# ATSAMD21_breakout_test.net
KiCad netlist of a schematic drawn in EAGLE
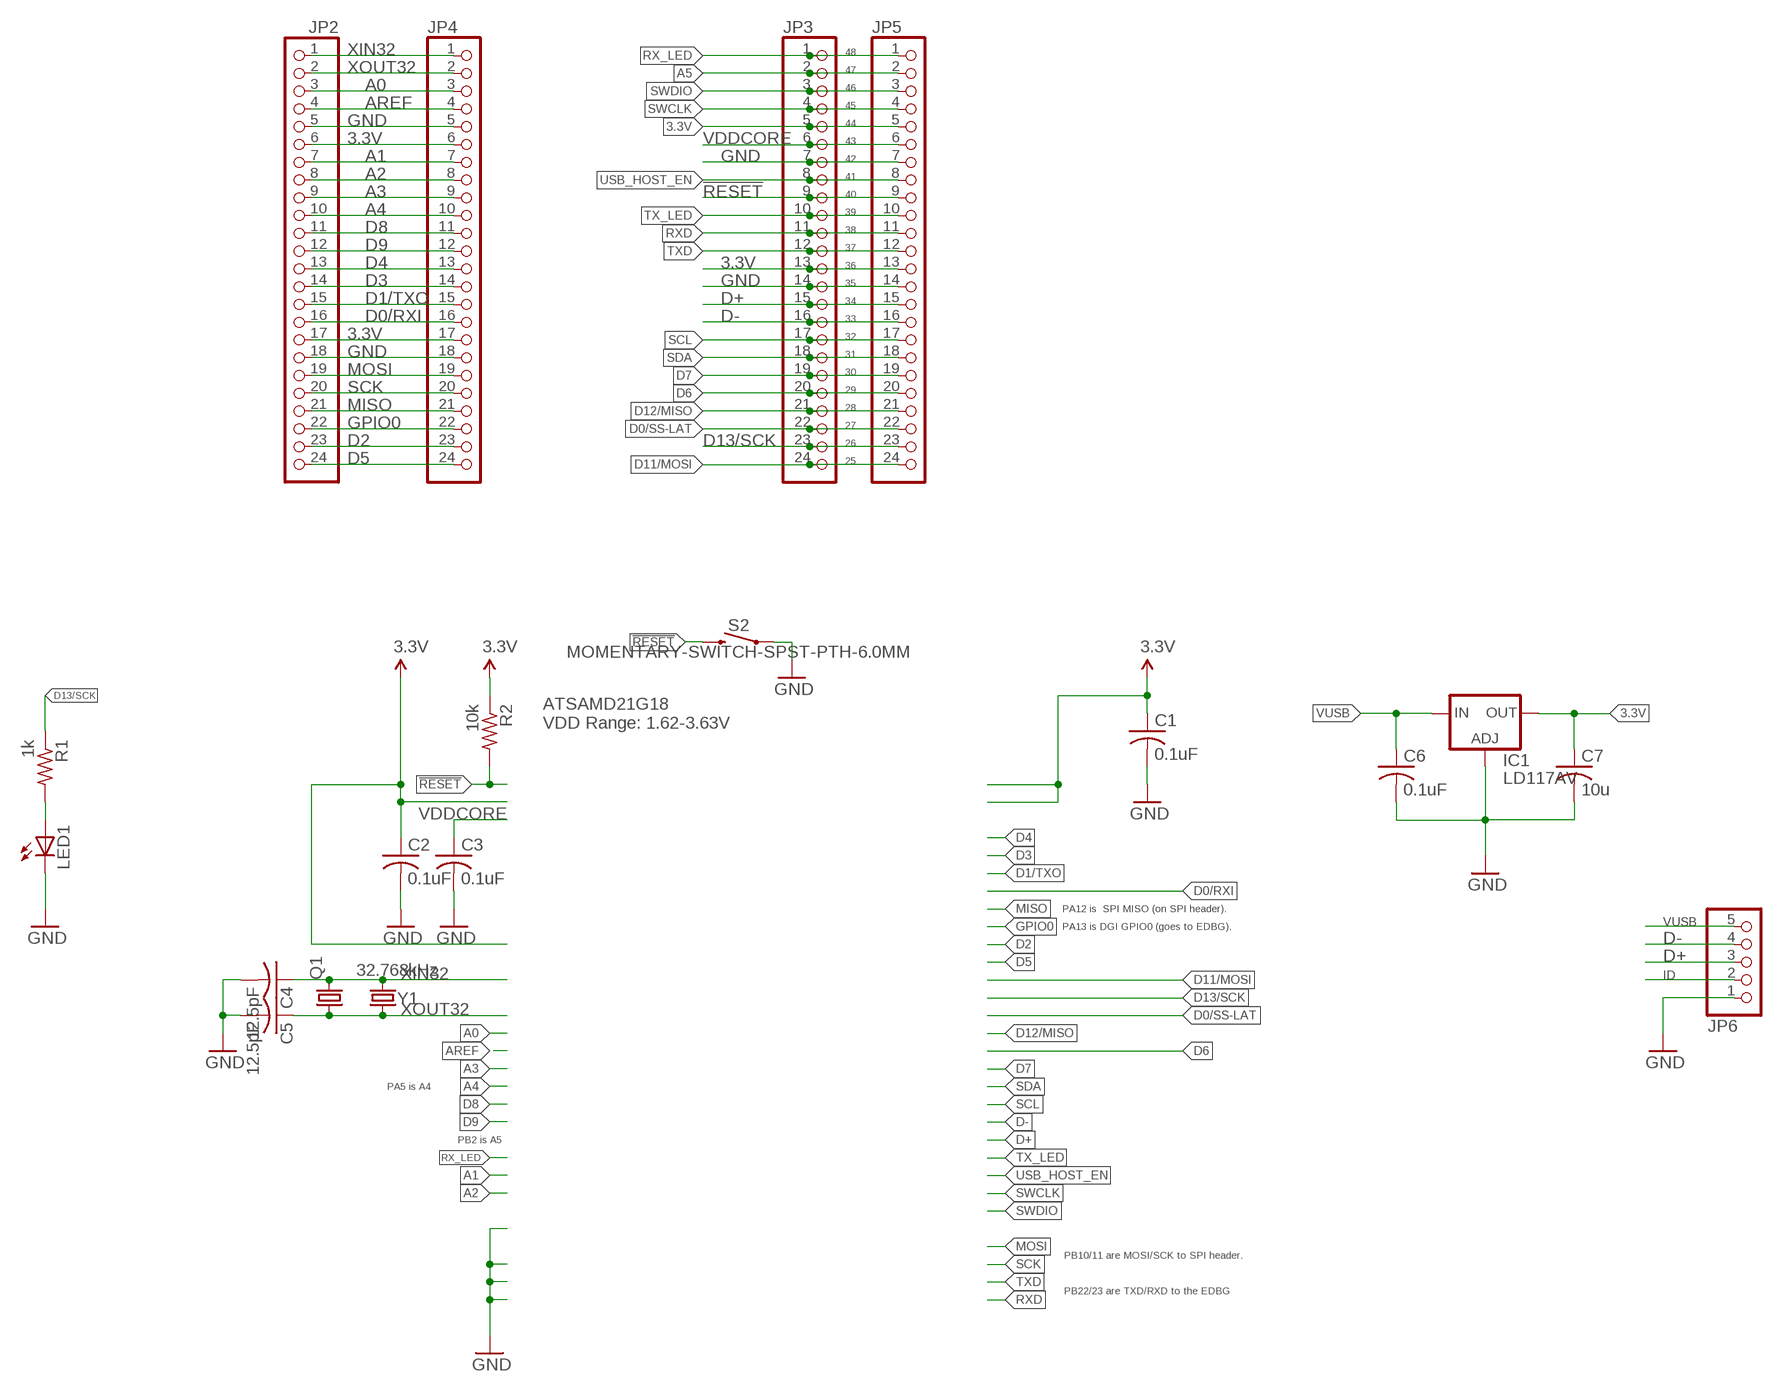
[diagram p0: schematic, sheet 1]

(export (version "E")
  (design (tool "Eeschema 10.0.6"))
  (components
    (comp (ref "C1")
      (value "0.1uF")
      (footprint "eagle-import:C025-024X044")
      (libsource (lib "eagle-import") (part "C-US025-024X044"))
    )
    (comp (ref "C2")
      (value "0.1uF")
      (footprint "eagle-import:C025-024X044")
      (libsource (lib "eagle-import") (part "C-US025-024X044"))
    )
    (comp (ref "C3")
      (value "0.1uF")
      (footprint "eagle-import:C025-024X044")
      (libsource (lib "eagle-import") (part "C-US025-024X044"))
    )
    (comp (ref "C4")
      (value "12.5pF")
      (footprint "eagle-import:C025-024X044")
      (libsource (lib "eagle-import") (part "C-US025-024X044"))
    )
    (comp (ref "C5")
      (value "12.5pF")
      (footprint "eagle-import:C025-024X044")
      (libsource (lib "eagle-import") (part "C-US025-024X044"))
    )
    (comp (ref "C6")
      (value "0.1uF")
      (footprint "eagle-import:C025-024X044")
      (libsource (lib "eagle-import") (part "C-US025-024X044"))
    )
    (comp (ref "C7")
      (value "10u")
      (footprint "eagle-import:C025-024X044")
      (libsource (lib "eagle-import") (part "C-US025-024X044"))
    )
    (comp (ref "IC1")
      (value "LD117AV")
      (footprint "eagle-import:TO220L1")
      (libsource (lib "eagle-import") (part "LD117A?V"))
    )
    (comp (ref "JP2")
      (value "PINHD-1X24")
      (footprint "eagle-import:1X24")
      (libsource (lib "eagle-import") (part "PINHD-1X24"))
    )
    (comp (ref "JP3")
      (value "PINHD-1X24")
      (footprint "eagle-import:1X24")
      (libsource (lib "eagle-import") (part "PINHD-1X24"))
    )
    (comp (ref "JP4")
      (value "PINHD-1X24")
      (footprint "eagle-import:1X24")
      (libsource (lib "eagle-import") (part "PINHD-1X24"))
    )
    (comp (ref "JP5")
      (value "PINHD-1X24")
      (footprint "eagle-import:1X24")
      (libsource (lib "eagle-import") (part "PINHD-1X24"))
    )
    (comp (ref "JP6")
      (value "PINHD-1X5")
      (footprint "eagle-import:1X05")
      (libsource (lib "eagle-import") (part "PINHD-1X5"))
    )
    (comp (ref "LED1")
      (value "LED3MM")
      (footprint "eagle-import:LED3MM")
      (libsource (lib "eagle-import") (part "LED3MM"))
    )
    (comp (ref "Q1")
      (value "CRYSTALTC26V")
      (footprint "eagle-import:TC26V")
      (libsource (lib "eagle-import") (part "CRYSTALTC26V"))
    )
    (comp (ref "R1")
      (value "1k")
      (footprint "eagle-import:0204_7")
      (libsource (lib "eagle-import") (part "R-US_0204/7"))
    )
    (comp (ref "R2")
      (value "10k")
      (footprint "eagle-import:0204_7")
      (libsource (lib "eagle-import") (part "R-US_0204/7"))
    )
    (comp (ref "S2")
      (value "MOMENTARY-SWITCH-SPST-PTH-6.0MM")
      (footprint "eagle-import:TACTILE_SWITCH_PTH_6.0MM")
      (libsource (lib "eagle-import") (part "MOMENTARY-SWITCH-SPST-PTH-6.0MM"))
    )
    (comp (ref "Y1")
      (value "32.768kHz")
      (footprint "eagle-import:CRYSTAL-SMD-3.2X1.5MM")
      (libsource (lib "eagle-import") (part "CRYSTAL3.2X1.5MM"))
    )
  )
  (nets
    (net (code "1") (name "/ID") (class "Default")
      (node (ref "JP6") (pin "2") (pinfunction "2_2") (pintype "passive"))
    )
    (net (code "2") (name "/VDDCORE") (class "Default")
      (node (ref "C3") (pin "1") (pinfunction "1_1") (pintype "passive"))
      (node (ref "JP3") (pin "6") (pinfunction "6_6") (pintype "passive"))
      (node (ref "JP5") (pin "6") (pinfunction "6_6") (pintype "passive"))
    )
    (net (code "3") (name "/XIN32") (class "Default")
      (node (ref "C4") (pin "1") (pinfunction "1_1") (pintype "passive"))
      (node (ref "JP2") (pin "1") (pinfunction "1_1") (pintype "passive"))
      (node (ref "JP4") (pin "1") (pinfunction "1_1") (pintype "passive"))
      (node (ref "Q1") (pin "2") (pinfunction "2_2") (pintype "passive"))
      (node (ref "Y1") (pin "P$2") (pinfunction "2_P$2") (pintype "passive"))
    )
    (net (code "4") (name "/XOUT32") (class "Default")
      (node (ref "C5") (pin "1") (pinfunction "1_1") (pintype "passive"))
      (node (ref "JP2") (pin "2") (pinfunction "2_2") (pintype "passive"))
      (node (ref "JP4") (pin "2") (pinfunction "2_2") (pintype "passive"))
      (node (ref "Q1") (pin "1") (pinfunction "1_1") (pintype "passive"))
      (node (ref "Y1") (pin "P$1") (pinfunction "1_P$1") (pintype "passive"))
    )
    (net (code "5") (name "/~{RESET}") (class "Default")
      (node (ref "JP3") (pin "9") (pinfunction "9_9") (pintype "passive"))
      (node (ref "JP5") (pin "9") (pinfunction "9_9") (pintype "passive"))
      (node (ref "R2") (pin "2") (pinfunction "2_2") (pintype "passive"))
      (node (ref "S2") (pin "3") (pinfunction "2_3") (pintype "passive"))
    )
    (net (code "6") (name "3.3V") (class "Default")
      (node (ref "C1") (pin "1") (pinfunction "1_1") (pintype "passive"))
      (node (ref "C2") (pin "1") (pinfunction "1_1") (pintype "passive"))
      (node (ref "C7") (pin "1") (pinfunction "1_1") (pintype "passive"))
      (node (ref "IC1") (pin "2") (pinfunction "OUT_2") (pintype "passive"))
      (node (ref "JP2") (pin "17") (pinfunction "17_17") (pintype "passive"))
      (node (ref "JP2") (pin "6") (pinfunction "6_6") (pintype "passive"))
      (node (ref "JP3") (pin "13") (pinfunction "13_13") (pintype "passive"))
      (node (ref "JP3") (pin "5") (pinfunction "5_5") (pintype "passive"))
      (node (ref "JP4") (pin "17") (pinfunction "17_17") (pintype "passive"))
      (node (ref "JP4") (pin "6") (pinfunction "6_6") (pintype "passive"))
      (node (ref "JP5") (pin "13") (pinfunction "13_13") (pintype "passive"))
      (node (ref "JP5") (pin "5") (pinfunction "5_5") (pintype "passive"))
      (node (ref "R2") (pin "1") (pinfunction "1_1") (pintype "passive"))
    )
    (net (code "7") (name "A0") (class "Default")
      (node (ref "JP2") (pin "3") (pinfunction "3_3") (pintype "passive"))
      (node (ref "JP4") (pin "3") (pinfunction "3_3") (pintype "passive"))
    )
    (net (code "8") (name "A1") (class "Default")
      (node (ref "JP2") (pin "7") (pinfunction "7_7") (pintype "passive"))
      (node (ref "JP4") (pin "7") (pinfunction "7_7") (pintype "passive"))
    )
    (net (code "9") (name "A2") (class "Default")
      (node (ref "JP2") (pin "8") (pinfunction "8_8") (pintype "passive"))
      (node (ref "JP4") (pin "8") (pinfunction "8_8") (pintype "passive"))
    )
    (net (code "10") (name "A3") (class "Default")
      (node (ref "JP2") (pin "9") (pinfunction "9_9") (pintype "passive"))
      (node (ref "JP4") (pin "9") (pinfunction "9_9") (pintype "passive"))
    )
    (net (code "11") (name "A4") (class "Default")
      (node (ref "JP2") (pin "10") (pinfunction "10_10") (pintype "passive"))
      (node (ref "JP4") (pin "10") (pinfunction "10_10") (pintype "passive"))
    )
    (net (code "12") (name "A5") (class "Default")
      (node (ref "JP3") (pin "2") (pinfunction "2_2") (pintype "passive"))
      (node (ref "JP5") (pin "2") (pinfunction "2_2") (pintype "passive"))
    )
    (net (code "13") (name "AREF") (class "Default")
      (node (ref "JP2") (pin "4") (pinfunction "4_4") (pintype "passive"))
      (node (ref "JP4") (pin "4") (pinfunction "4_4") (pintype "passive"))
    )
    (net (code "14") (name "D+") (class "Default")
      (node (ref "JP3") (pin "15") (pinfunction "15_15") (pintype "passive"))
      (node (ref "JP5") (pin "15") (pinfunction "15_15") (pintype "passive"))
      (node (ref "JP6") (pin "3") (pinfunction "3_3") (pintype "passive"))
    )
    (net (code "15") (name "D-") (class "Default")
      (node (ref "JP3") (pin "16") (pinfunction "16_16") (pintype "passive"))
      (node (ref "JP5") (pin "16") (pinfunction "16_16") (pintype "passive"))
      (node (ref "JP6") (pin "4") (pinfunction "4_4") (pintype "passive"))
    )
    (net (code "16") (name "D0{slash}RXI") (class "Default")
      (node (ref "JP2") (pin "16") (pinfunction "16_16") (pintype "passive"))
      (node (ref "JP4") (pin "16") (pinfunction "16_16") (pintype "passive"))
    )
    (net (code "17") (name "D0{slash}SS-LAT") (class "Default")
      (node (ref "JP3") (pin "22") (pinfunction "22_22") (pintype "passive"))
      (node (ref "JP5") (pin "22") (pinfunction "22_22") (pintype "passive"))
    )
    (net (code "18") (name "D1{slash}TXO") (class "Default")
      (node (ref "JP2") (pin "15") (pinfunction "15_15") (pintype "passive"))
      (node (ref "JP4") (pin "15") (pinfunction "15_15") (pintype "passive"))
    )
    (net (code "19") (name "D2") (class "Default")
      (node (ref "JP2") (pin "23") (pinfunction "23_23") (pintype "passive"))
      (node (ref "JP4") (pin "23") (pinfunction "23_23") (pintype "passive"))
    )
    (net (code "20") (name "D3") (class "Default")
      (node (ref "JP2") (pin "14") (pinfunction "14_14") (pintype "passive"))
      (node (ref "JP4") (pin "14") (pinfunction "14_14") (pintype "passive"))
    )
    (net (code "21") (name "D4") (class "Default")
      (node (ref "JP2") (pin "13") (pinfunction "13_13") (pintype "passive"))
      (node (ref "JP4") (pin "13") (pinfunction "13_13") (pintype "passive"))
    )
    (net (code "22") (name "D5") (class "Default")
      (node (ref "JP2") (pin "24") (pinfunction "24_24") (pintype "passive"))
      (node (ref "JP4") (pin "24") (pinfunction "24_24") (pintype "passive"))
    )
    (net (code "23") (name "D6") (class "Default")
      (node (ref "JP3") (pin "20") (pinfunction "20_20") (pintype "passive"))
      (node (ref "JP5") (pin "20") (pinfunction "20_20") (pintype "passive"))
    )
    (net (code "24") (name "D7") (class "Default")
      (node (ref "JP3") (pin "19") (pinfunction "19_19") (pintype "passive"))
      (node (ref "JP5") (pin "19") (pinfunction "19_19") (pintype "passive"))
    )
    (net (code "25") (name "D8") (class "Default")
      (node (ref "JP2") (pin "11") (pinfunction "11_11") (pintype "passive"))
      (node (ref "JP4") (pin "11") (pinfunction "11_11") (pintype "passive"))
    )
    (net (code "26") (name "D9") (class "Default")
      (node (ref "JP2") (pin "12") (pinfunction "12_12") (pintype "passive"))
      (node (ref "JP4") (pin "12") (pinfunction "12_12") (pintype "passive"))
    )
    (net (code "27") (name "D11{slash}MOSI") (class "Default")
      (node (ref "JP3") (pin "24") (pinfunction "24_24") (pintype "passive"))
      (node (ref "JP5") (pin "24") (pinfunction "24_24") (pintype "passive"))
    )
    (net (code "28") (name "D12{slash}MISO") (class "Default")
      (node (ref "JP3") (pin "21") (pinfunction "21_21") (pintype "passive"))
      (node (ref "JP5") (pin "21") (pinfunction "21_21") (pintype "passive"))
    )
    (net (code "29") (name "D13{slash}SCK") (class "Default")
      (node (ref "JP3") (pin "23") (pinfunction "23_23") (pintype "passive"))
      (node (ref "JP5") (pin "23") (pinfunction "23_23") (pintype "passive"))
      (node (ref "R1") (pin "1") (pinfunction "1_1") (pintype "passive"))
    )
    (net (code "30") (name "GND") (class "Default")
      (node (ref "C1") (pin "2") (pinfunction "2_2") (pintype "passive"))
      (node (ref "C2") (pin "2") (pinfunction "2_2") (pintype "passive"))
      (node (ref "C3") (pin "2") (pinfunction "2_2") (pintype "passive"))
      (node (ref "C4") (pin "2") (pinfunction "2_2") (pintype "passive"))
      (node (ref "C5") (pin "2") (pinfunction "2_2") (pintype "passive"))
      (node (ref "C6") (pin "2") (pinfunction "2_2") (pintype "passive"))
      (node (ref "C7") (pin "2") (pinfunction "2_2") (pintype "passive"))
      (node (ref "IC1") (pin "1") (pinfunction "ADJ_1") (pintype "input"))
      (node (ref "JP2") (pin "18") (pinfunction "18_18") (pintype "passive"))
      (node (ref "JP2") (pin "5") (pinfunction "5_5") (pintype "passive"))
      (node (ref "JP3") (pin "14") (pinfunction "14_14") (pintype "passive"))
      (node (ref "JP3") (pin "7") (pinfunction "7_7") (pintype "passive"))
      (node (ref "JP4") (pin "18") (pinfunction "18_18") (pintype "passive"))
      (node (ref "JP4") (pin "5") (pinfunction "5_5") (pintype "passive"))
      (node (ref "JP5") (pin "14") (pinfunction "14_14") (pintype "passive"))
      (node (ref "JP5") (pin "7") (pinfunction "7_7") (pintype "passive"))
      (node (ref "JP6") (pin "1") (pinfunction "1_1") (pintype "passive"))
      (node (ref "LED1") (pin "K") (pinfunction "C_K") (pintype "passive"))
      (node (ref "S2") (pin "1") (pinfunction "1_1") (pintype "passive"))
    )
    (net (code "31") (name "GPIO0") (class "Default")
      (node (ref "JP2") (pin "22") (pinfunction "22_22") (pintype "passive"))
      (node (ref "JP4") (pin "22") (pinfunction "22_22") (pintype "passive"))
    )
    (net (code "32") (name "MISO") (class "Default")
      (node (ref "JP2") (pin "21") (pinfunction "21_21") (pintype "passive"))
      (node (ref "JP4") (pin "21") (pinfunction "21_21") (pintype "passive"))
    )
    (net (code "33") (name "MOSI") (class "Default")
      (node (ref "JP2") (pin "19") (pinfunction "19_19") (pintype "passive"))
      (node (ref "JP4") (pin "19") (pinfunction "19_19") (pintype "passive"))
    )
    (net (code "34") (name "Net-(LED1-PadA)") (class "Default")
      (node (ref "LED1") (pin "A") (pinfunction "A_A") (pintype "passive"))
      (node (ref "R1") (pin "2") (pinfunction "2_2") (pintype "passive"))
    )
    (net (code "35") (name "RXD") (class "Default")
      (node (ref "JP3") (pin "11") (pinfunction "11_11") (pintype "passive"))
      (node (ref "JP5") (pin "11") (pinfunction "11_11") (pintype "passive"))
    )
    (net (code "36") (name "RX_LED") (class "Default")
      (node (ref "JP3") (pin "1") (pinfunction "1_1") (pintype "passive"))
      (node (ref "JP5") (pin "1") (pinfunction "1_1") (pintype "passive"))
    )
    (net (code "37") (name "SCK") (class "Default")
      (node (ref "JP2") (pin "20") (pinfunction "20_20") (pintype "passive"))
      (node (ref "JP4") (pin "20") (pinfunction "20_20") (pintype "passive"))
    )
    (net (code "38") (name "SCL") (class "Default")
      (node (ref "JP3") (pin "17") (pinfunction "17_17") (pintype "passive"))
      (node (ref "JP5") (pin "17") (pinfunction "17_17") (pintype "passive"))
    )
    (net (code "39") (name "SDA") (class "Default")
      (node (ref "JP3") (pin "18") (pinfunction "18_18") (pintype "passive"))
      (node (ref "JP5") (pin "18") (pinfunction "18_18") (pintype "passive"))
    )
    (net (code "40") (name "SWCLK") (class "Default")
      (node (ref "JP3") (pin "4") (pinfunction "4_4") (pintype "passive"))
      (node (ref "JP5") (pin "4") (pinfunction "4_4") (pintype "passive"))
    )
    (net (code "41") (name "SWDIO") (class "Default")
      (node (ref "JP3") (pin "3") (pinfunction "3_3") (pintype "passive"))
      (node (ref "JP5") (pin "3") (pinfunction "3_3") (pintype "passive"))
    )
    (net (code "42") (name "TXD") (class "Default")
      (node (ref "JP3") (pin "12") (pinfunction "12_12") (pintype "passive"))
      (node (ref "JP5") (pin "12") (pinfunction "12_12") (pintype "passive"))
    )
    (net (code "43") (name "TX_LED") (class "Default")
      (node (ref "JP3") (pin "10") (pinfunction "10_10") (pintype "passive"))
      (node (ref "JP5") (pin "10") (pinfunction "10_10") (pintype "passive"))
    )
    (net (code "44") (name "USB_HOST_EN") (class "Default")
      (node (ref "JP3") (pin "8") (pinfunction "8_8") (pintype "passive"))
      (node (ref "JP5") (pin "8") (pinfunction "8_8") (pintype "passive"))
    )
    (net (code "45") (name "VUSB") (class "Default")
      (node (ref "C6") (pin "1") (pinfunction "1_1") (pintype "passive"))
      (node (ref "IC1") (pin "3") (pinfunction "IN_3") (pintype "input"))
      (node (ref "JP6") (pin "5") (pinfunction "5_5") (pintype "passive"))
    )
  )
)
